# 01-USER_IO.net
KiCad netlist of a schematic drawn in Altium Designer
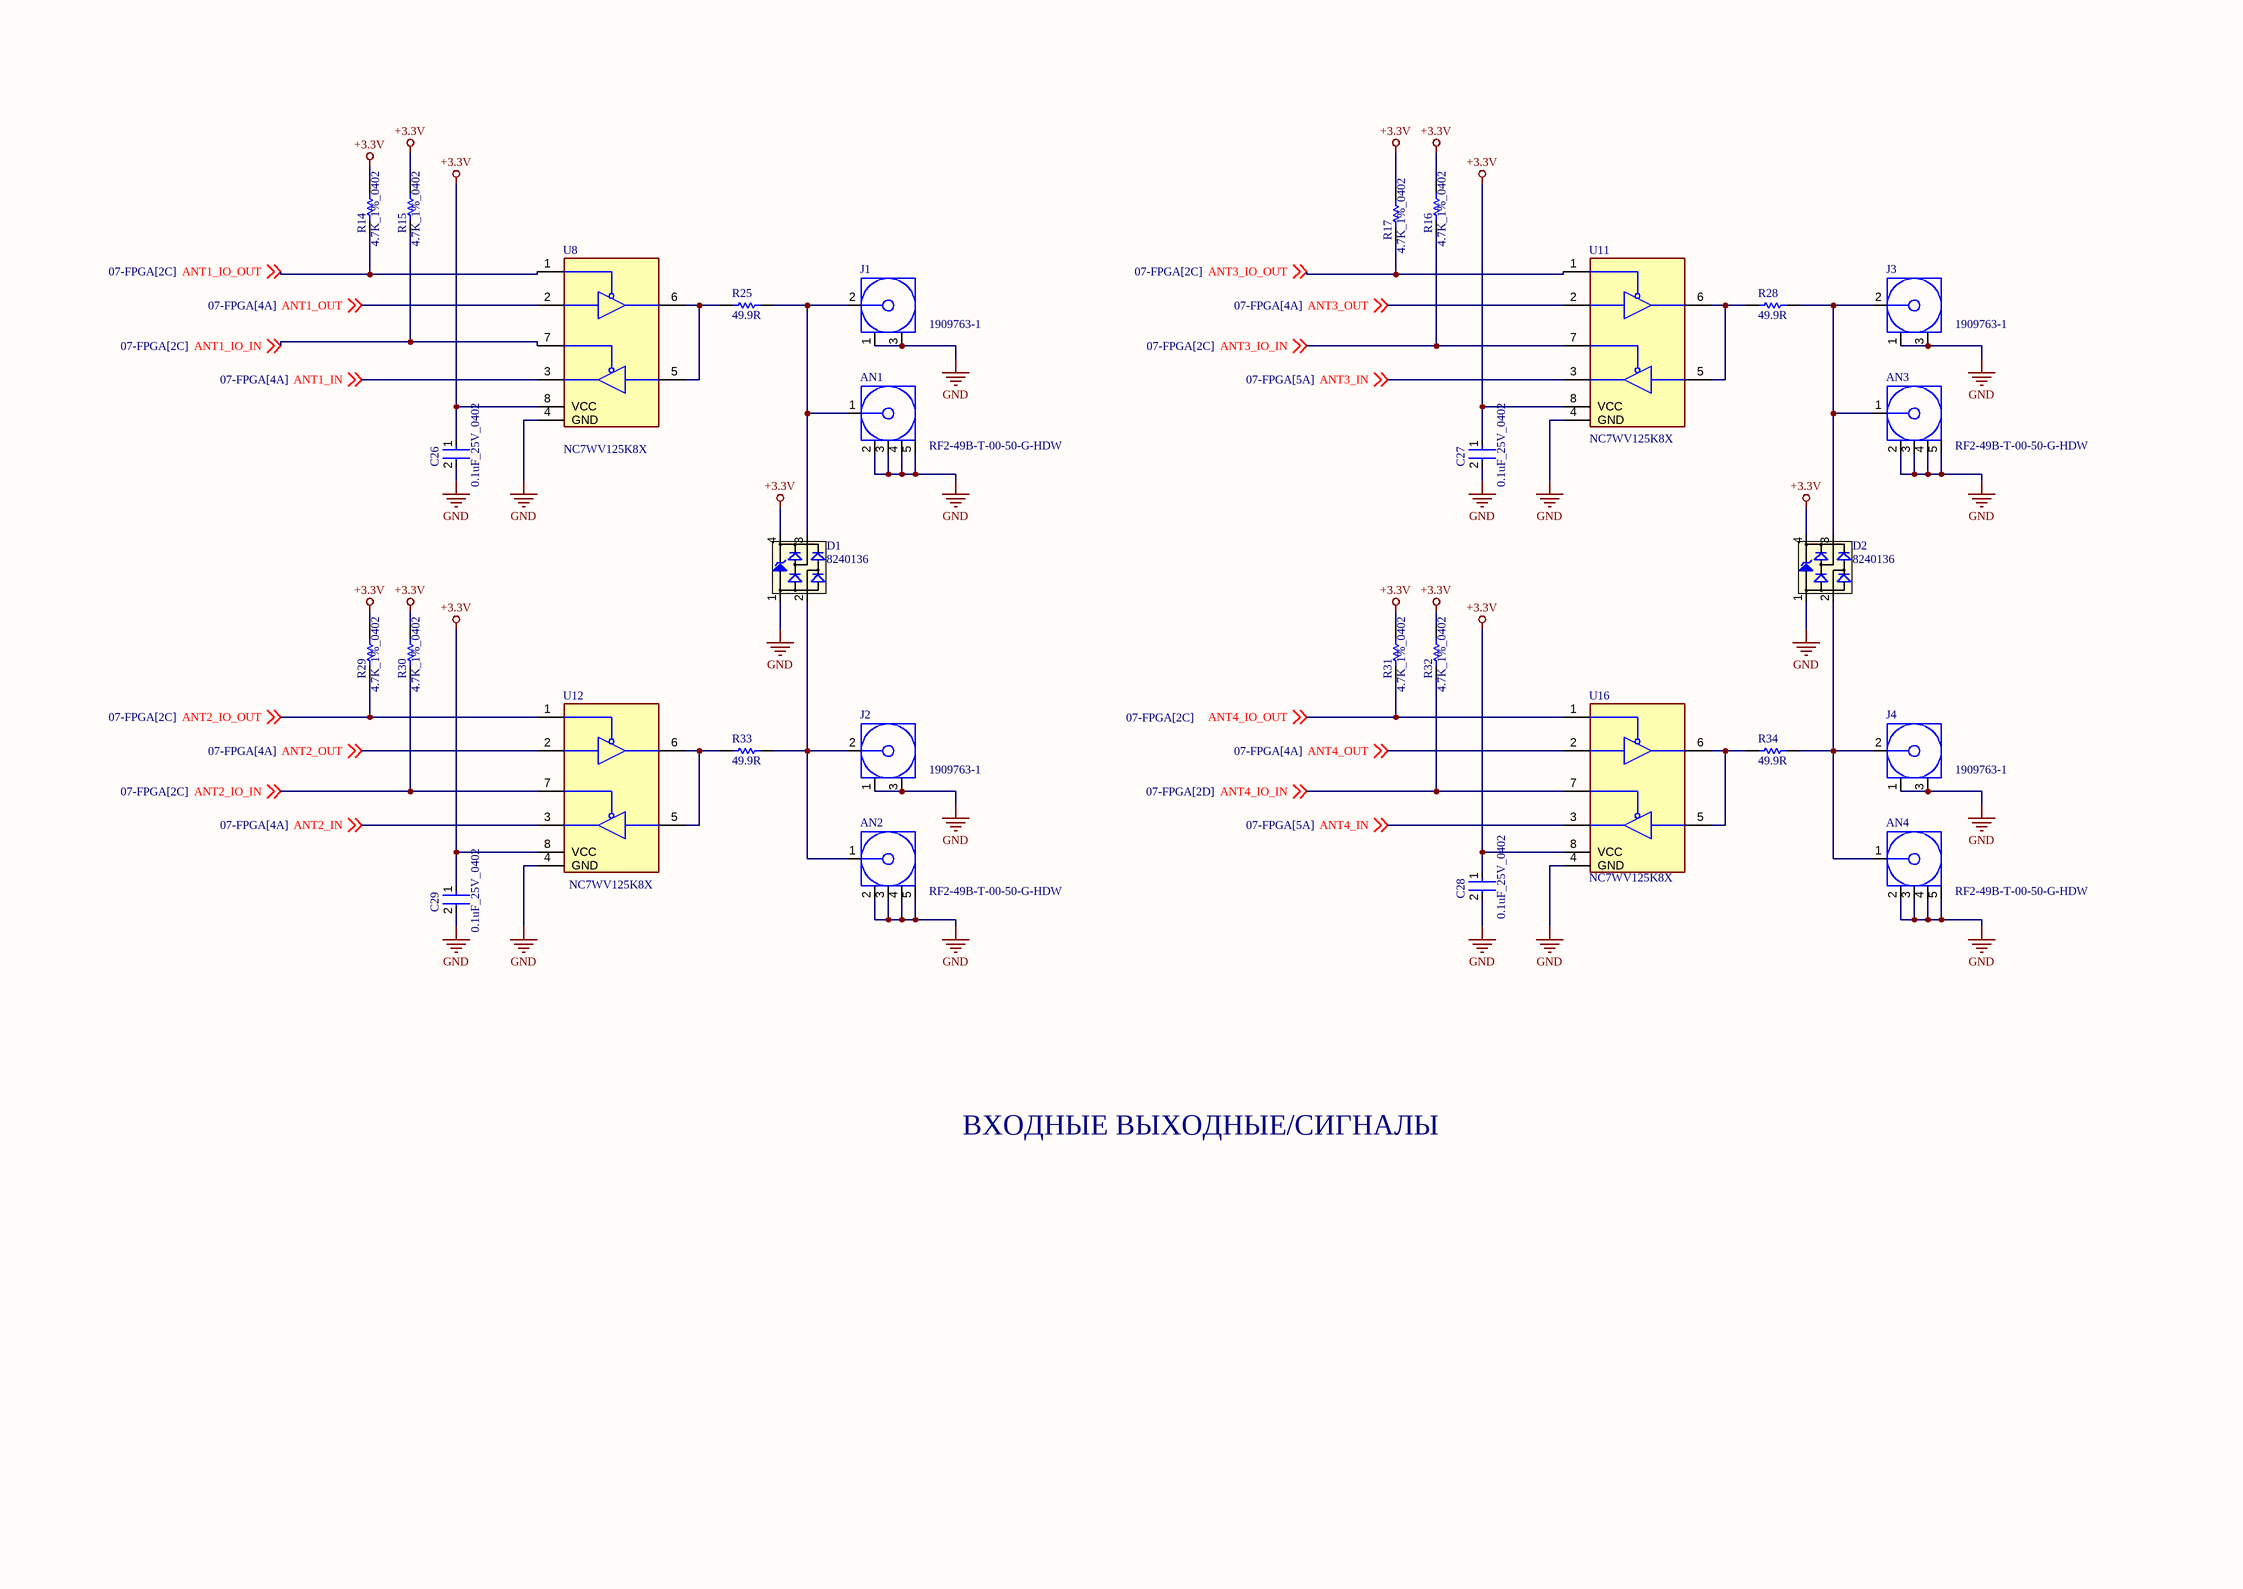
[diagram p0: 01-USER_IO.SchDoc]

(export (version "E")
  (design (tool "Eeschema 10.0.6"))
  (components
    (comp (ref "AN1")
      (value "RF2-49B-T-00-50-G-HDW")
      (footprint "AMPH-901-143-6RFX_V")
      (description "Coaxial connector, 50 Ohm, -65 to 165 degC, 5-Pin THD, RoHS, Bulk")
      (fields (field (name "MANUFACTURER") "Amphenol"))
      (libsource (lib "Altium Content Vault") (part "CN-S-4F-RF5"))
    )
    (comp (ref "AN2")
      (value "RF2-49B-T-00-50-G-HDW")
      (footprint "AMPH-901-143-6RFX_V")
      (description "Coaxial connector, 50 Ohm, -65 to 165 degC, 5-Pin THD, RoHS, Bulk")
      (fields (field (name "MANUFACTURER") "Amphenol"))
      (libsource (lib "Altium Content Vault") (part "CN-S-4F-RF5"))
    )
    (comp (ref "AN3")
      (value "RF2-49B-T-00-50-G-HDW")
      (footprint "AMPH-901-143-6RFX_V")
      (description "Coaxial connector, 50 Ohm, -65 to 165 degC, 5-Pin THD, RoHS, Bulk")
      (fields (field (name "MANUFACTURER") "Amphenol"))
      (libsource (lib "Altium Content Vault") (part "CN-S-4F-RF5"))
    )
    (comp (ref "AN4")
      (value "RF2-49B-T-00-50-G-HDW")
      (footprint "AMPH-901-143-6RFX_V")
      (description "Coaxial connector, 50 Ohm, -65 to 165 degC, 5-Pin THD, RoHS, Bulk")
      (fields (field (name "MANUFACTURER") "Amphenol"))
      (libsource (lib "Altium Content Vault") (part "CN-S-4F-RF5"))
    )
    (comp (ref "C26")
      (value "0.1uF_25V_0402")
      (footprint "FP-0402-L_1_0_1-W_0_5_0_1-IPC_C")
      (description "General Purpose Ceramic Capacitor, 0402, 100nF, 10%, X7R, 15%, 25V")
      (fields (field (name "VOLTAGE") "25V") (field (name "TOLERANCE") "10%"))
      (libsource (lib "Altium Content Vault") (part "b4654b650e69147ec39a6b967a45e02"))
    )
    (comp (ref "C27")
      (value "0.1uF_25V_0402")
      (footprint "FP-0402-L_1_0_1-W_0_5_0_1-IPC_C")
      (description "General Purpose Ceramic Capacitor, 0402, 100nF, 10%, X7R, 15%, 25V")
      (fields (field (name "VOLTAGE") "25V") (field (name "TOLERANCE") "10%"))
      (libsource (lib "Altium Content Vault") (part "b4654b650e69147ec39a6b967a45e02"))
    )
    (comp (ref "C28")
      (value "0.1uF_25V_0402")
      (footprint "FP-0402-L_1_0_1-W_0_5_0_1-IPC_C")
      (description "General Purpose Ceramic Capacitor, 0402, 100nF, 10%, X7R, 15%, 25V")
      (fields (field (name "VOLTAGE") "25V") (field (name "TOLERANCE") "10%"))
      (libsource (lib "Altium Content Vault") (part "b4654b650e69147ec39a6b967a45e02"))
    )
    (comp (ref "C29")
      (value "0.1uF_25V_0402")
      (footprint "FP-0402-L_1_0_1-W_0_5_0_1-IPC_C")
      (description "General Purpose Ceramic Capacitor, 0402, 100nF, 10%, X7R, 15%, 25V")
      (fields (field (name "VOLTAGE") "25V") (field (name "TOLERANCE") "10%"))
      (libsource (lib "Altium Content Vault") (part "b4654b650e69147ec39a6b967a45e02"))
    )
    (comp (ref "D1")
      (value "8240136")
      (footprint "SOT143-4L")
      (description "TVS Diode WE-TVS-HS, VRWM=3.3V")
      (fields (field (name "MANUFACTURER") "Wuerth Elektronik"))
      (libsource (lib "Altium Content Vault") (part "WE-TVS-HS-4"))
    )
    (comp (ref "D2")
      (value "8240136")
      (footprint "SOT143-4L")
      (description "TVS Diode WE-TVS-HS, VRWM=3.3V")
      (fields (field (name "MANUFACTURER") "Wuerth Elektronik"))
      (libsource (lib "Altium Content Vault") (part "WE-TVS-HS-4"))
    )
    (comp (ref "J1")
      (value "1909763-1")
      (footprint "TECO-1909763-1_V")
      (description "Ultra Miniature Coaxial Connector Jack, 60 V, 50 Ohm, -40 to 90 degC, RoHS, Tape and Reel")
      (fields (field (name "MANUFACTURER") "TE Connectivity"))
      (libsource (lib "Altium Content Vault") (part "CN-1P-M-RF3"))
    )
    (comp (ref "J2")
      (value "1909763-1")
      (footprint "TECO-1909763-1_V")
      (description "Ultra Miniature Coaxial Connector Jack, 60 V, 50 Ohm, -40 to 90 degC, RoHS, Tape and Reel")
      (fields (field (name "MANUFACTURER") "TE Connectivity"))
      (libsource (lib "Altium Content Vault") (part "CN-1P-M-RF3"))
    )
    (comp (ref "J3")
      (value "1909763-1")
      (footprint "TECO-1909763-1_V")
      (description "Ultra Miniature Coaxial Connector Jack, 60 V, 50 Ohm, -40 to 90 degC, RoHS, Tape and Reel")
      (fields (field (name "MANUFACTURER") "TE Connectivity"))
      (libsource (lib "Altium Content Vault") (part "CN-1P-M-RF3"))
    )
    (comp (ref "J4")
      (value "1909763-1")
      (footprint "TECO-1909763-1_V")
      (description "Ultra Miniature Coaxial Connector Jack, 60 V, 50 Ohm, -40 to 90 degC, RoHS, Tape and Reel")
      (fields (field (name "MANUFACTURER") "TE Connectivity"))
      (libsource (lib "Altium Content Vault") (part "CN-1P-M-RF3"))
    )
    (comp (ref "R14")
      (value "4.7K_1%_0402")
      (footprint "RESC1005X40X25NL10T10")
      (fields (field (name "MANUFACTURER") "Bourns") (field (name "PART NUMBER") "CR0402-FX-4701GLF"))
      (libsource (lib "Altium Content Vault") (part "RES"))
    )
    (comp (ref "R15")
      (value "4.7K_1%_0402")
      (footprint "RESC1005X40X25NL10T10")
      (fields (field (name "MANUFACTURER") "Bourns") (field (name "PART NUMBER") "CR0402-FX-4701GLF"))
      (libsource (lib "Altium Content Vault") (part "RES"))
    )
    (comp (ref "R16")
      (value "4.7K_1%_0402")
      (footprint "RESC1005X40X25NL10T10")
      (fields (field (name "MANUFACTURER") "Bourns") (field (name "PART NUMBER") "CR0402-FX-4701GLF"))
      (libsource (lib "Altium Content Vault") (part "RES"))
    )
    (comp (ref "R17")
      (value "4.7K_1%_0402")
      (footprint "RESC1005X40X25NL10T10")
      (fields (field (name "MANUFACTURER") "Bourns") (field (name "PART NUMBER") "CR0402-FX-4701GLF"))
      (libsource (lib "Altium Content Vault") (part "RES"))
    )
    (comp (ref "R25")
      (value "49.9R")
      (footprint "RESC1608X55X25NL10T15")
      (libsource (lib "Altium Content Vault") (part "RES-2"))
    )
    (comp (ref "R28")
      (value "49.9R")
      (footprint "RESC1608X55X25NL10T15")
      (libsource (lib "Altium Content Vault") (part "RES-2"))
    )
    (comp (ref "R29")
      (value "4.7K_1%_0402")
      (footprint "RESC1005X40X25NL10T10")
      (fields (field (name "MANUFACTURER") "Bourns") (field (name "PART NUMBER") "CR0402-FX-4701GLF"))
      (libsource (lib "Altium Content Vault") (part "RES"))
    )
    (comp (ref "R30")
      (value "4.7K_1%_0402")
      (footprint "RESC1005X40X25NL10T10")
      (fields (field (name "MANUFACTURER") "Bourns") (field (name "PART NUMBER") "CR0402-FX-4701GLF"))
      (libsource (lib "Altium Content Vault") (part "RES"))
    )
    (comp (ref "R31")
      (value "4.7K_1%_0402")
      (footprint "RESC1005X40X25NL10T10")
      (fields (field (name "MANUFACTURER") "Bourns") (field (name "PART NUMBER") "CR0402-FX-4701GLF"))
      (libsource (lib "Altium Content Vault") (part "RES"))
    )
    (comp (ref "R32")
      (value "4.7K_1%_0402")
      (footprint "RESC1005X40X25NL10T10")
      (fields (field (name "MANUFACTURER") "Bourns") (field (name "PART NUMBER") "CR0402-FX-4701GLF"))
      (libsource (lib "Altium Content Vault") (part "RES"))
    )
    (comp (ref "R33")
      (value "49.9R")
      (footprint "RESC1608X55X25NL10T15")
      (libsource (lib "Altium Content Vault") (part "RES-2"))
    )
    (comp (ref "R34")
      (value "49.9R")
      (footprint "RESC1608X55X25NL10T15")
      (libsource (lib "Altium Content Vault") (part "RES-2"))
    )
    (comp (ref "U8")
      (value "NC7WV125K8X")
      (footprint "SamacSys:SOP50P310X90-8N")
      (description "Integrated Circuit")
      (fields (field (name "MOUSER PART NUMBER") "512-NC7WV125K8X"))
      (libsource (lib "SamacSys") (part "NC7WV125K8X"))
    )
    (comp (ref "U11")
      (value "NC7WV125K8X")
      (footprint "SamacSys:SOP50P310X90-8N")
      (description "Integrated Circuit")
      (fields (field (name "MOUSER PART NUMBER") "512-NC7WV125K8X"))
      (libsource (lib "SamacSys") (part "NC7WV125K8X"))
    )
    (comp (ref "U12")
      (value "NC7WV125K8X")
      (footprint "SamacSys:SOP50P310X90-8N")
      (description "Integrated Circuit")
      (fields (field (name "MOUSER PART NUMBER") "512-NC7WV125K8X"))
      (libsource (lib "SamacSys") (part "NC7WV125K8X"))
    )
    (comp (ref "U16")
      (value "NC7WV125K8X")
      (footprint "SamacSys:SOP50P310X90-8N")
      (description "Integrated Circuit")
      (fields (field (name "MOUSER PART NUMBER") "512-NC7WV125K8X"))
      (libsource (lib "SamacSys") (part "NC7WV125K8X"))
    )
  )
  (nets
    (net (code "1") (name "+3.3V") (class "Default")
      (node (ref "C26") (pin "1") (pinfunction "1_1") (pintype "passive"))
      (node (ref "C27") (pin "1") (pinfunction "1_1") (pintype "passive"))
      (node (ref "C28") (pin "1") (pinfunction "1_1") (pintype "passive"))
      (node (ref "C29") (pin "1") (pinfunction "1_1") (pintype "passive"))
      (node (ref "D1") (pin "4") (pinfunction "VDD_4") (pintype "passive"))
      (node (ref "D2") (pin "4") (pinfunction "VDD_4") (pintype "passive"))
      (node (ref "R14") (pin "1") (pinfunction "1_1") (pintype "passive"))
      (node (ref "R15") (pin "1") (pinfunction "1_1") (pintype "passive"))
      (node (ref "R16") (pin "1") (pinfunction "1_1") (pintype "passive"))
      (node (ref "R17") (pin "1") (pinfunction "1_1") (pintype "passive"))
      (node (ref "R29") (pin "1") (pinfunction "1_1") (pintype "passive"))
      (node (ref "R30") (pin "1") (pinfunction "1_1") (pintype "passive"))
      (node (ref "R31") (pin "1") (pinfunction "1_1") (pintype "passive"))
      (node (ref "R32") (pin "1") (pinfunction "1_1") (pintype "passive"))
      (node (ref "U11") (pin "8") (pinfunction "VCC_8") (pintype "passive"))
      (node (ref "U12") (pin "8") (pinfunction "VCC_8") (pintype "passive"))
      (node (ref "U16") (pin "8") (pinfunction "VCC_8") (pintype "passive"))
      (node (ref "U8") (pin "8") (pinfunction "VCC_8") (pintype "passive"))
    )
    (net (code "2") (name "ANT1_IN") (class "Default") (node (ref "U8") (pin "3") (pintype "passive")))
    (net (code "3") (name "ANT1_IO_IN") (class "Default")
      (node (ref "R15") (pin "2") (pinfunction "2_2") (pintype "passive"))
      (node (ref "U8") (pin "7") (pintype "passive"))
    )
    (net (code "4") (name "ANT1_IO_OUT") (class "Default")
      (node (ref "R14") (pin "2") (pinfunction "2_2") (pintype "passive"))
      (node (ref "U8") (pin "1") (pintype "passive"))
    )
    (net (code "5") (name "ANT1_OUT") (class "Default") (node (ref "U8") (pin "2") (pintype "passive")))
    (net (code "6") (name "ANT2_IN") (class "Default") (node (ref "U12") (pin "3") (pintype "passive")))
    (net (code "7") (name "ANT2_IO_IN") (class "Default")
      (node (ref "R30") (pin "2") (pinfunction "2_2") (pintype "passive"))
      (node (ref "U12") (pin "7") (pintype "passive"))
    )
    (net (code "8") (name "ANT2_IO_OUT") (class "Default")
      (node (ref "R29") (pin "2") (pinfunction "2_2") (pintype "passive"))
      (node (ref "U12") (pin "1") (pintype "passive"))
    )
    (net (code "9") (name "ANT2_OUT") (class "Default") (node (ref "U12") (pin "2") (pintype "passive")))
    (net (code "10") (name "ANT3_IN") (class "Default") (node (ref "U11") (pin "3") (pintype "passive")))
    (net (code "11") (name "ANT3_IO_IN") (class "Default")
      (node (ref "R16") (pin "2") (pinfunction "2_2") (pintype "passive"))
      (node (ref "U11") (pin "7") (pintype "passive"))
    )
    (net (code "12") (name "ANT3_IO_OUT") (class "Default")
      (node (ref "R17") (pin "2") (pinfunction "2_2") (pintype "passive"))
      (node (ref "U11") (pin "1") (pintype "passive"))
    )
    (net (code "13") (name "ANT3_OUT") (class "Default") (node (ref "U11") (pin "2") (pintype "passive")))
    (net (code "14") (name "ANT4_IN") (class "Default") (node (ref "U16") (pin "3") (pintype "passive")))
    (net (code "15") (name "ANT4_IO_IN") (class "Default")
      (node (ref "R32") (pin "2") (pinfunction "2_2") (pintype "passive"))
      (node (ref "U16") (pin "7") (pintype "passive"))
    )
    (net (code "16") (name "ANT4_IO_OUT") (class "Default")
      (node (ref "R31") (pin "2") (pinfunction "2_2") (pintype "passive"))
      (node (ref "U16") (pin "1") (pintype "passive"))
    )
    (net (code "17") (name "ANT4_OUT") (class "Default") (node (ref "U16") (pin "2") (pintype "passive")))
    (net (code "18") (name "GND") (class "Default")
      (node (ref "AN1") (pin "2") (pinfunction "2_2") (pintype "passive"))
      (node (ref "AN1") (pin "3") (pinfunction "3_3") (pintype "passive"))
      (node (ref "AN1") (pin "4") (pinfunction "4_4") (pintype "passive"))
      (node (ref "AN1") (pin "5") (pinfunction "5_5") (pintype "passive"))
      (node (ref "AN2") (pin "2") (pinfunction "2_2") (pintype "passive"))
      (node (ref "AN2") (pin "3") (pinfunction "3_3") (pintype "passive"))
      (node (ref "AN2") (pin "4") (pinfunction "4_4") (pintype "passive"))
      (node (ref "AN2") (pin "5") (pinfunction "5_5") (pintype "passive"))
      (node (ref "AN3") (pin "2") (pinfunction "2_2") (pintype "passive"))
      (node (ref "AN3") (pin "3") (pinfunction "3_3") (pintype "passive"))
      (node (ref "AN3") (pin "4") (pinfunction "4_4") (pintype "passive"))
      (node (ref "AN3") (pin "5") (pinfunction "5_5") (pintype "passive"))
      (node (ref "AN4") (pin "2") (pinfunction "2_2") (pintype "passive"))
      (node (ref "AN4") (pin "3") (pinfunction "3_3") (pintype "passive"))
      (node (ref "AN4") (pin "4") (pinfunction "4_4") (pintype "passive"))
      (node (ref "AN4") (pin "5") (pinfunction "5_5") (pintype "passive"))
      (node (ref "C26") (pin "2") (pinfunction "2_2") (pintype "passive"))
      (node (ref "C27") (pin "2") (pinfunction "2_2") (pintype "passive"))
      (node (ref "C28") (pin "2") (pinfunction "2_2") (pintype "passive"))
      (node (ref "C29") (pin "2") (pinfunction "2_2") (pintype "passive"))
      (node (ref "D1") (pin "1") (pinfunction "GND_1") (pintype "passive"))
      (node (ref "D2") (pin "1") (pinfunction "GND_1") (pintype "passive"))
      (node (ref "J1") (pin "1") (pinfunction "1_1") (pintype "passive"))
      (node (ref "J1") (pin "3") (pinfunction "3_3") (pintype "passive"))
      (node (ref "J2") (pin "1") (pinfunction "1_1") (pintype "passive"))
      (node (ref "J2") (pin "3") (pinfunction "3_3") (pintype "passive"))
      (node (ref "J3") (pin "1") (pinfunction "1_1") (pintype "passive"))
      (node (ref "J3") (pin "3") (pinfunction "3_3") (pintype "passive"))
      (node (ref "J4") (pin "1") (pinfunction "1_1") (pintype "passive"))
      (node (ref "J4") (pin "3") (pinfunction "3_3") (pintype "passive"))
      (node (ref "U11") (pin "4") (pinfunction "GND_4") (pintype "passive"))
      (node (ref "U12") (pin "4") (pinfunction "GND_4") (pintype "passive"))
      (node (ref "U16") (pin "4") (pinfunction "GND_4") (pintype "passive"))
      (node (ref "U8") (pin "4") (pinfunction "GND_4") (pintype "passive"))
    )
    (net (code "19") (name "Net-(D1-I{slash}O1)") (class "Default")
      (node (ref "AN2") (pin "1") (pinfunction "1_1") (pintype "passive"))
      (node (ref "D1") (pin "2") (pinfunction "I/O1_2") (pintype "passive"))
      (node (ref "J2") (pin "2") (pinfunction "2_2") (pintype "passive"))
      (node (ref "R33") (pin "2") (pinfunction "2_2") (pintype "passive"))
    )
    (net (code "20") (name "Net-(D1-I{slash}O2)") (class "Default")
      (node (ref "AN1") (pin "1") (pinfunction "1_1") (pintype "passive"))
      (node (ref "D1") (pin "3") (pinfunction "I/O2_3") (pintype "passive"))
      (node (ref "J1") (pin "2") (pinfunction "2_2") (pintype "passive"))
      (node (ref "R25") (pin "2") (pinfunction "2_2") (pintype "passive"))
    )
    (net (code "21") (name "Net-(D2-I{slash}O1)") (class "Default")
      (node (ref "AN4") (pin "1") (pinfunction "1_1") (pintype "passive"))
      (node (ref "D2") (pin "2") (pinfunction "I/O1_2") (pintype "passive"))
      (node (ref "J4") (pin "2") (pinfunction "2_2") (pintype "passive"))
      (node (ref "R34") (pin "2") (pinfunction "2_2") (pintype "passive"))
    )
    (net (code "22") (name "Net-(D2-I{slash}O2)") (class "Default")
      (node (ref "AN3") (pin "1") (pinfunction "1_1") (pintype "passive"))
      (node (ref "D2") (pin "3") (pinfunction "I/O2_3") (pintype "passive"))
      (node (ref "J3") (pin "2") (pinfunction "2_2") (pintype "passive"))
      (node (ref "R28") (pin "2") (pinfunction "2_2") (pintype "passive"))
    )
    (net (code "23") (name "Net-(R25-Pad1)") (class "Default")
      (node (ref "R25") (pin "1") (pinfunction "1_1") (pintype "passive"))
      (node (ref "U8") (pin "5") (pintype "passive"))
      (node (ref "U8") (pin "6") (pintype "passive"))
    )
    (net (code "24") (name "Net-(R28-Pad1)") (class "Default")
      (node (ref "R28") (pin "1") (pinfunction "1_1") (pintype "passive"))
      (node (ref "U11") (pin "5") (pintype "passive"))
      (node (ref "U11") (pin "6") (pintype "passive"))
    )
    (net (code "25") (name "Net-(R33-Pad1)") (class "Default")
      (node (ref "R33") (pin "1") (pinfunction "1_1") (pintype "passive"))
      (node (ref "U12") (pin "5") (pintype "passive"))
      (node (ref "U12") (pin "6") (pintype "passive"))
    )
    (net (code "26") (name "Net-(R34-Pad1)") (class "Default")
      (node (ref "R34") (pin "1") (pinfunction "1_1") (pintype "passive"))
      (node (ref "U16") (pin "5") (pintype "passive"))
      (node (ref "U16") (pin "6") (pintype "passive"))
    )
  )
)
